# BareBonesArduino.net
KiCad netlist of a schematic drawn in EAGLE
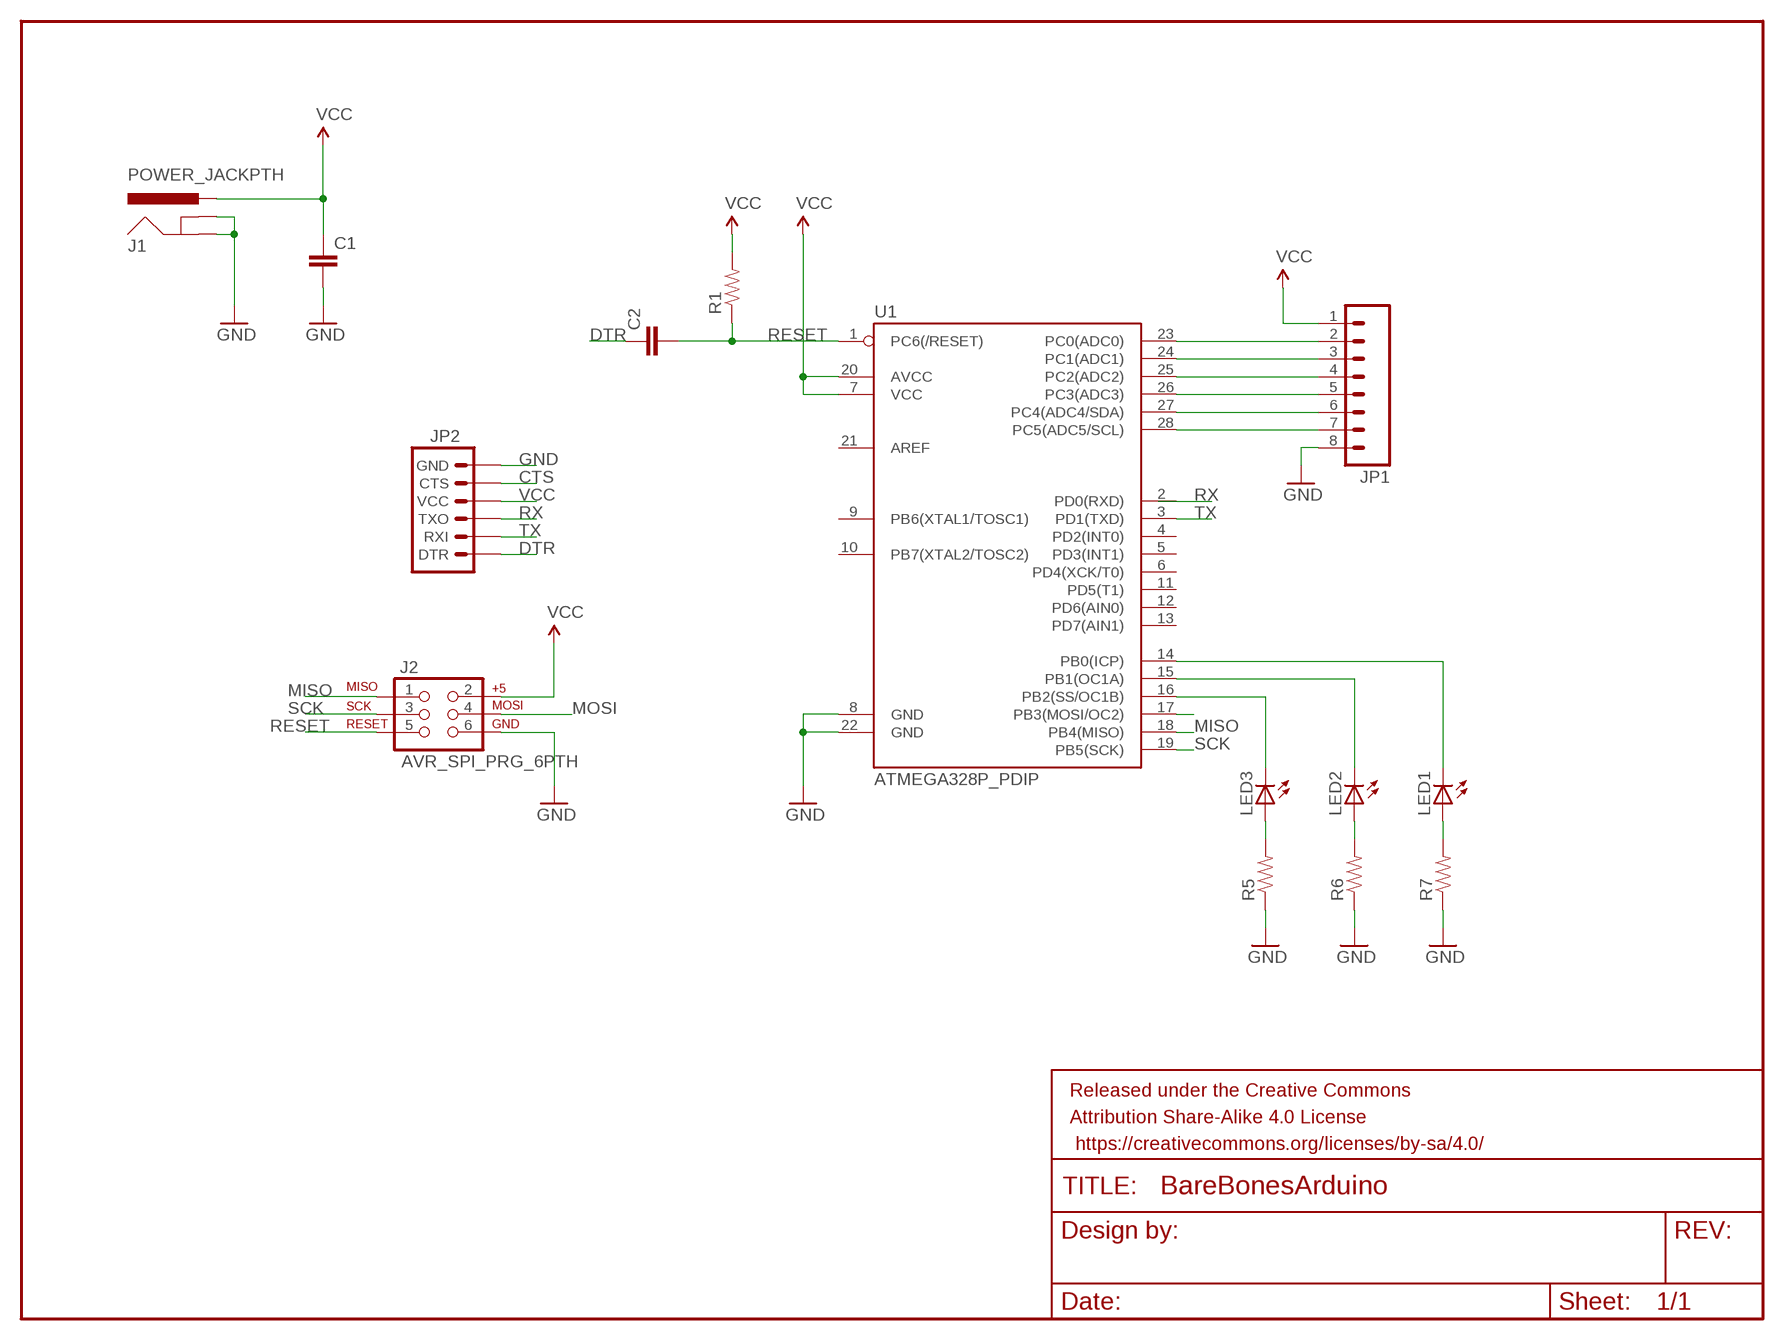
[diagram p0: schematic, sheet 1]

(export (version "E")
  (design (tool "Eeschema 10.0.6"))
  (components
    (comp (ref "C1")
      (value "CAPPTH")
      (footprint "eagle-import:CAP-PTH-SMALL")
      (libsource (lib "eagle-import") (part "CAPPTH"))
    )
    (comp (ref "C2")
      (value "CAPPTH")
      (footprint "eagle-import:CAP-PTH-SMALL")
      (libsource (lib "eagle-import") (part "CAPPTH"))
    )
    (comp (ref "FRAME1")
      (value "FRAME-LETTER")
      (footprint "eagle-import:CREATIVE_COMMONS")
      (libsource (lib "eagle-import") (part "FRAME-LETTER"))
    )
    (comp (ref "J1")
      (value "POWER_JACKPTH")
      (footprint "eagle-import:POWER_JACK_PTH")
      (libsource (lib "eagle-import") (part "POWER_JACKPTH"))
    )
    (comp (ref "J2")
      (value "AVR_SPI_PRG_6PTH")
      (footprint "eagle-import:2X3")
      (libsource (lib "eagle-import") (part "AVR_SPI_PRG_6PTH"))
    )
    (comp (ref "JP1")
      (value "M081X08")
      (footprint "eagle-import:1X08")
      (libsource (lib "eagle-import") (part "M081X08"))
    )
    (comp (ref "JP2")
      (value "ARDUINO_SERIAL_PROGRAMPTH")
      (footprint "eagle-import:1X06")
      (libsource (lib "eagle-import") (part "ARDUINO_SERIAL_PROGRAMPTH"))
    )
    (comp (ref "LED1")
      (value "LED5MM")
      (footprint "eagle-import:LED5MM")
      (libsource (lib "eagle-import") (part "LED5MM"))
    )
    (comp (ref "LED2")
      (value "LED5MM")
      (footprint "eagle-import:LED5MM")
      (libsource (lib "eagle-import") (part "LED5MM"))
    )
    (comp (ref "LED3")
      (value "LED5MM")
      (footprint "eagle-import:LED5MM")
      (libsource (lib "eagle-import") (part "LED5MM"))
    )
    (comp (ref "R1")
      (value "RESISTORPTH-1/4W")
      (footprint "eagle-import:AXIAL-0.4")
      (libsource (lib "eagle-import") (part "RESISTORPTH-1/4W"))
    )
    (comp (ref "R5")
      (value "RESISTORPTH-1/4W")
      (footprint "eagle-import:AXIAL-0.4")
      (libsource (lib "eagle-import") (part "RESISTORPTH-1/4W"))
    )
    (comp (ref "R6")
      (value "RESISTORPTH-1/4W")
      (footprint "eagle-import:AXIAL-0.4")
      (libsource (lib "eagle-import") (part "RESISTORPTH-1/4W"))
    )
    (comp (ref "R7")
      (value "RESISTORPTH-1/4W")
      (footprint "eagle-import:AXIAL-0.4")
      (libsource (lib "eagle-import") (part "RESISTORPTH-1/4W"))
    )
    (comp (ref "U1")
      (value "ATMEGA328P_PDIP")
      (footprint "eagle-import:DIL28-3")
      (libsource (lib "eagle-import") (part "ATMEGA328P_PDIP"))
    )
  )
  (nets
    (net (code "1") (name "/CTS") (class "Default")
      (node (ref "JP2") (pin "5") (pinfunction "CTS_5") (pintype "passive"))
    )
    (net (code "2") (name "/DTR") (class "Default")
      (node (ref "C2") (pin "1") (pinfunction "1_1") (pintype "passive"))
      (node (ref "JP2") (pin "1") (pinfunction "DTR_1") (pintype "passive"))
    )
    (net (code "3") (name "/MISO") (class "Default")
      (node (ref "J2") (pin "1") (pinfunction "1_1") (pintype "passive"))
      (node (ref "U1") (pin "18") (pinfunction "PB4(MISO)_18") (pintype "bidirectional"))
    )
    (net (code "4") (name "/MOSI") (class "Default")
      (node (ref "J2") (pin "4") (pinfunction "4_4") (pintype "passive"))
      (node (ref "LED3") (pin "K") (pinfunction "C_K") (pintype "passive"))
      (node (ref "U1") (pin "16") (pinfunction "PB2(SS/OC1B)_16") (pintype "bidirectional"))
      (node (ref "U1") (pin "17") (pinfunction "PB3(MOSI/OC2)_17") (pintype "bidirectional"))
    )
    (net (code "5") (name "/RESET") (class "Default")
      (node (ref "C2") (pin "2") (pinfunction "2_2") (pintype "passive"))
      (node (ref "J2") (pin "5") (pinfunction "5_5") (pintype "passive"))
      (node (ref "R1") (pin "P$1") (pinfunction "1_P$1") (pintype "passive"))
      (node (ref "U1") (pin "1") (pinfunction "PC6(/RESET)_1") (pintype "bidirectional"))
    )
    (net (code "6") (name "/RX") (class "Default")
      (node (ref "JP2") (pin "3") (pinfunction "TXO_3") (pintype "passive"))
    )
    (net (code "7") (name "/SCK") (class "Default")
      (node (ref "J2") (pin "3") (pinfunction "3_3") (pintype "passive"))
      (node (ref "U1") (pin "19") (pinfunction "PB5(SCK)_19") (pintype "bidirectional"))
    )
    (net (code "8") (name "/TX") (class "Default")
      (node (ref "JP2") (pin "2") (pinfunction "RXI_2") (pintype "passive"))
      (node (ref "U1") (pin "3") (pinfunction "PD1(TXD)_3") (pintype "bidirectional"))
    )
    (net (code "9") (name "GND") (class "Default")
      (node (ref "C1") (pin "2") (pinfunction "2_2") (pintype "passive"))
      (node (ref "J1") (pin "GND") (pinfunction "GND_GND") (pintype "bidirectional"))
      (node (ref "J1") (pin "GNDBREAK") (pinfunction "GNDBREAK_GNDBREAK") (pintype "bidirectional"))
      (node (ref "J2") (pin "6") (pinfunction "6_6") (pintype "passive"))
      (node (ref "JP1") (pin "8") (pinfunction "8_8") (pintype "passive"))
      (node (ref "JP2") (pin "6") (pinfunction "GND_6") (pintype "passive"))
      (node (ref "R5") (pin "P$1") (pinfunction "1_P$1") (pintype "passive"))
      (node (ref "R6") (pin "P$1") (pinfunction "1_P$1") (pintype "passive"))
      (node (ref "R7") (pin "P$1") (pinfunction "1_P$1") (pintype "passive"))
      (node (ref "U1") (pin "22") (pinfunction "GND_22") (pintype "bidirectional"))
      (node (ref "U1") (pin "8") (pinfunction "GND_8") (pintype "bidirectional"))
    )
    (net (code "10") (name "Net-(LED1-C)") (class "Default")
      (node (ref "LED1") (pin "K") (pinfunction "C_K") (pintype "passive"))
      (node (ref "U1") (pin "14") (pinfunction "PB0(ICP)_14") (pintype "bidirectional"))
    )
    (net (code "11") (name "Net-(LED2-C)") (class "Default")
      (node (ref "LED2") (pin "K") (pinfunction "C_K") (pintype "passive"))
      (node (ref "U1") (pin "15") (pinfunction "PB1(OC1A)_15") (pintype "bidirectional"))
    )
    (net (code "12") (name "Net-(R5-2)") (class "Default")
      (node (ref "LED3") (pin "A") (pinfunction "A_A") (pintype "passive"))
      (node (ref "R5") (pin "P$2") (pinfunction "2_P$2") (pintype "passive"))
    )
    (net (code "13") (name "Net-(R6-2)") (class "Default")
      (node (ref "LED2") (pin "A") (pinfunction "A_A") (pintype "passive"))
      (node (ref "R6") (pin "P$2") (pinfunction "2_P$2") (pintype "passive"))
    )
    (net (code "14") (name "Net-(R7-2)") (class "Default")
      (node (ref "LED1") (pin "A") (pinfunction "A_A") (pintype "passive"))
      (node (ref "R7") (pin "P$2") (pinfunction "2_P$2") (pintype "passive"))
    )
    (net (code "15") (name "Net-(U1-PC0(ADC0))") (class "Default")
      (node (ref "JP1") (pin "2") (pinfunction "2_2") (pintype "passive"))
      (node (ref "U1") (pin "23") (pinfunction "PC0(ADC0)_23") (pintype "bidirectional"))
    )
    (net (code "16") (name "Net-(U1-PC1(ADC1))") (class "Default")
      (node (ref "JP1") (pin "3") (pinfunction "3_3") (pintype "passive"))
      (node (ref "U1") (pin "24") (pinfunction "PC1(ADC1)_24") (pintype "bidirectional"))
    )
    (net (code "17") (name "Net-(U1-PC2(ADC2))") (class "Default")
      (node (ref "JP1") (pin "4") (pinfunction "4_4") (pintype "passive"))
      (node (ref "U1") (pin "25") (pinfunction "PC2(ADC2)_25") (pintype "bidirectional"))
    )
    (net (code "18") (name "Net-(U1-PC3(ADC3))") (class "Default")
      (node (ref "JP1") (pin "5") (pinfunction "5_5") (pintype "passive"))
      (node (ref "U1") (pin "26") (pinfunction "PC3(ADC3)_26") (pintype "bidirectional"))
    )
    (net (code "19") (name "Net-(U1-PC4(ADC4{slash}SDA))") (class "Default")
      (node (ref "JP1") (pin "6") (pinfunction "6_6") (pintype "passive"))
      (node (ref "U1") (pin "27") (pinfunction "PC4(ADC4/SDA)_27") (pintype "bidirectional"))
    )
    (net (code "20") (name "Net-(U1-PC5(ADC5{slash}SCL))") (class "Default")
      (node (ref "JP1") (pin "7") (pinfunction "7_7") (pintype "passive"))
      (node (ref "U1") (pin "28") (pinfunction "PC5(ADC5/SCL)_28") (pintype "bidirectional"))
    )
    (net (code "21") (name "VCC") (class "Default")
      (node (ref "C1") (pin "1") (pinfunction "1_1") (pintype "passive"))
      (node (ref "J1") (pin "PWR") (pinfunction "PWR_PWR") (pintype "bidirectional"))
      (node (ref "J2") (pin "2") (pinfunction "2_2") (pintype "passive"))
      (node (ref "JP1") (pin "1") (pinfunction "1_1") (pintype "passive"))
      (node (ref "JP2") (pin "4") (pinfunction "VCC_4") (pintype "passive"))
      (node (ref "R1") (pin "P$2") (pinfunction "2_P$2") (pintype "passive"))
      (node (ref "U1") (pin "20") (pinfunction "AVCC_20") (pintype "bidirectional"))
      (node (ref "U1") (pin "7") (pinfunction "VCC_7") (pintype "bidirectional"))
    )
    (net (code "22") (name "unconnected-(U1-AREF-Pad21)") (class "Default")
      (node (ref "U1") (pin "21") (pinfunction "AREF_21") (pintype "bidirectional"))
    )
    (net (code "23") (name "unconnected-(U1-PB6(XTAL1{slash}TOSC1)-Pad9)") (class "Default")
      (node (ref "U1") (pin "9") (pinfunction "PB6(XTAL1/TOSC1)_9") (pintype "bidirectional"))
    )
    (net (code "24") (name "unconnected-(U1-PB7(XTAL2{slash}TOSC2)-Pad10)") (class "Default")
      (node (ref "U1") (pin "10") (pinfunction "PB7(XTAL2/TOSC2)_10") (pintype "bidirectional"))
    )
    (net (code "25") (name "unconnected-(U1-PD0(RXD)-Pad2)") (class "Default")
      (node (ref "U1") (pin "2") (pinfunction "PD0(RXD)_2") (pintype "bidirectional"))
    )
    (net (code "26") (name "unconnected-(U1-PD2(INT0)-Pad4)") (class "Default")
      (node (ref "U1") (pin "4") (pinfunction "PD2(INT0)_4") (pintype "bidirectional"))
    )
    (net (code "27") (name "unconnected-(U1-PD3(INT1)-Pad5)") (class "Default")
      (node (ref "U1") (pin "5") (pinfunction "PD3(INT1)_5") (pintype "bidirectional"))
    )
    (net (code "28") (name "unconnected-(U1-PD4(XCK{slash}T0)-Pad6)") (class "Default")
      (node (ref "U1") (pin "6") (pinfunction "PD4(XCK/T0)_6") (pintype "bidirectional"))
    )
    (net (code "29") (name "unconnected-(U1-PD5(T1)-Pad11)") (class "Default")
      (node (ref "U1") (pin "11") (pinfunction "PD5(T1)_11") (pintype "bidirectional"))
    )
    (net (code "30") (name "unconnected-(U1-PD6(AIN0)-Pad12)") (class "Default")
      (node (ref "U1") (pin "12") (pinfunction "PD6(AIN0)_12") (pintype "bidirectional"))
    )
    (net (code "31") (name "unconnected-(U1-PD7(AIN1)-Pad13)") (class "Default")
      (node (ref "U1") (pin "13") (pinfunction "PD7(AIN1)_13") (pintype "bidirectional"))
    )
  )
)
